# A5000_BasicBackplane.net
KiCad netlist of a schematic drawn in Altium Designer
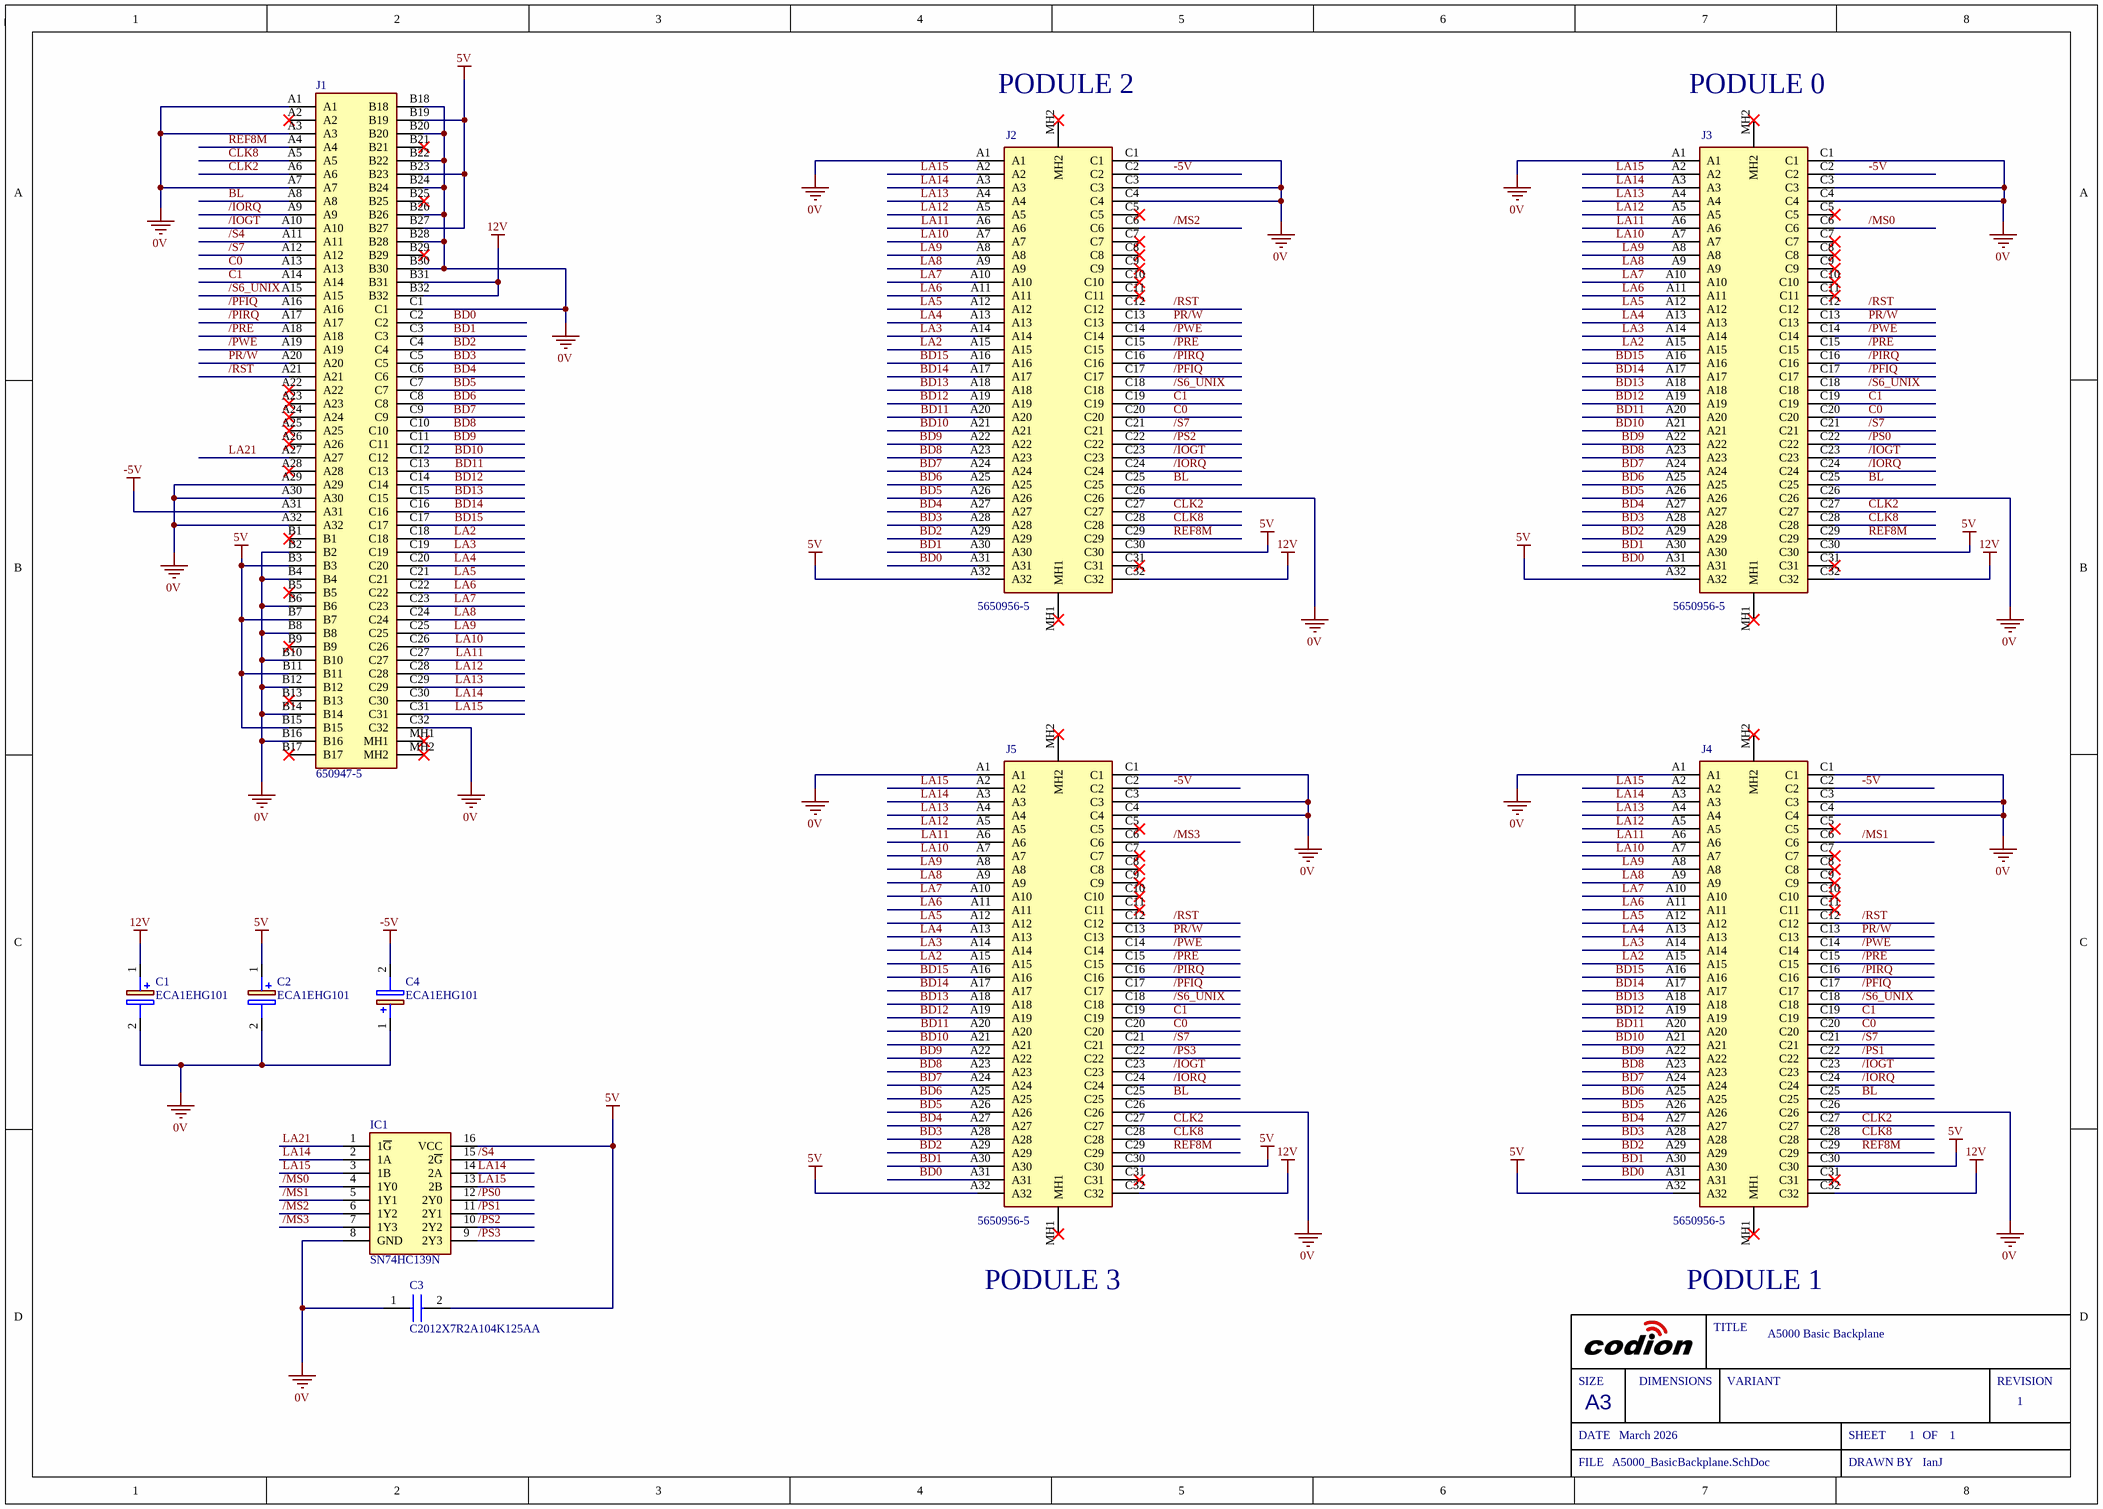
[diagram p0: A5000_BasicBackplane.SchDoc]

(export (version "E")
  (design (tool "Eeschema 10.0.6"))
  (components
    (comp (ref "C1")
      (value "ECA1EHG101")
      (footprint "SamacSys:CAPPRD250W55D630H1220")
      (description "Capacitor Polarised")
      (libsource (lib "*") (part "ECA1EHG101"))
    )
    (comp (ref "C2")
      (value "ECA1EHG101")
      (footprint "SamacSys:CAPPRD250W55D630H1220")
      (description "Capacitor Polarised")
      (libsource (lib "*") (part "ECA1EHG101"))
    )
    (comp (ref "C3")
      (value "C2012X7R2A104K125AA")
      (footprint "SamacSys:CAPC2012X145N")
      (description "Capacitor")
      (fields (field (name "MOUSER PART NUMBER") "810-C2012X7R2A104K"))
      (libsource (lib "*") (part "C2012X7R2A104K125AA"))
    )
    (comp (ref "C4")
      (value "ECA1EHG101")
      (footprint "SamacSys:CAPPRD250W55D630H1220")
      (description "Capacitor Polarised")
      (libsource (lib "") (part "ECA1EHG101_1"))
    )
    (comp (ref "IC1")
      (value "SN74HC139N")
      (footprint "SamacSys:DIP794W53P254L1930H508Q16N")
      (description "Integrated Circuit")
      (fields (field (name "MOUSER PART NUMBER") "595-SN74HC139N"))
      (libsource (lib "*") (part "SN74HC139N"))
    )
    (comp (ref "J1")
      (value "650947-5")
      (footprint "SamacSys:6509475")
      (description "Connector")
      (fields (field (name "MOUSER PART NUMBER") "571-6509475"))
      (libsource (lib "*") (part "650947-5"))
    )
    (comp (ref "J2")
      (value "5650956-5")
      (footprint "SamacSys:56509565")
      (description "Connector")
      (fields (field (name "MOUSER PART NUMBER") "571-5650956-5"))
      (libsource (lib "*") (part "5650956-5"))
    )
    (comp (ref "J3")
      (value "5650956-5")
      (footprint "SamacSys:56509565")
      (description "Connector")
      (fields (field (name "MOUSER PART NUMBER") "571-5650956-5"))
      (libsource (lib "*") (part "5650956-5"))
    )
    (comp (ref "J4")
      (value "5650956-5")
      (footprint "SamacSys:56509565")
      (description "Connector")
      (fields (field (name "MOUSER PART NUMBER") "571-5650956-5"))
      (libsource (lib "*") (part "5650956-5"))
    )
    (comp (ref "J5")
      (value "5650956-5")
      (footprint "SamacSys:56509565")
      (description "Connector")
      (fields (field (name "MOUSER PART NUMBER") "571-5650956-5"))
      (libsource (lib "*") (part "5650956-5"))
    )
  )
  (nets
    (net (code "1") (name "-5V") (class "Default")
      (node (ref "C4") (pin "2") (pinfunction "-_2") (pintype "passive"))
      (node (ref "J1") (pin "A31") (pinfunction "A31_A31") (pintype "passive"))
      (node (ref "J2") (pin "C2") (pinfunction "C2_C2") (pintype "passive"))
      (node (ref "J3") (pin "C2") (pinfunction "C2_C2") (pintype "passive"))
      (node (ref "J4") (pin "C2") (pinfunction "C2_C2") (pintype "passive"))
      (node (ref "J5") (pin "C2") (pinfunction "C2_C2") (pintype "passive"))
    )
    (net (code "2") (name "/BD0") (class "Default")
      (node (ref "J1") (pin "C2") (pinfunction "C2_C2") (pintype "passive"))
      (node (ref "J2") (pin "A31") (pinfunction "A31_A31") (pintype "passive"))
      (node (ref "J3") (pin "A31") (pinfunction "A31_A31") (pintype "passive"))
      (node (ref "J4") (pin "A31") (pinfunction "A31_A31") (pintype "passive"))
      (node (ref "J5") (pin "A31") (pinfunction "A31_A31") (pintype "passive"))
    )
    (net (code "3") (name "/BD1") (class "Default")
      (node (ref "J1") (pin "C3") (pinfunction "C3_C3") (pintype "passive"))
      (node (ref "J2") (pin "A30") (pinfunction "A30_A30") (pintype "passive"))
      (node (ref "J3") (pin "A30") (pinfunction "A30_A30") (pintype "passive"))
      (node (ref "J4") (pin "A30") (pinfunction "A30_A30") (pintype "passive"))
      (node (ref "J5") (pin "A30") (pinfunction "A30_A30") (pintype "passive"))
    )
    (net (code "4") (name "/BD2") (class "Default")
      (node (ref "J1") (pin "C4") (pinfunction "C4_C4") (pintype "passive"))
      (node (ref "J2") (pin "A29") (pinfunction "A29_A29") (pintype "passive"))
      (node (ref "J3") (pin "A29") (pinfunction "A29_A29") (pintype "passive"))
      (node (ref "J4") (pin "A29") (pinfunction "A29_A29") (pintype "passive"))
      (node (ref "J5") (pin "A29") (pinfunction "A29_A29") (pintype "passive"))
    )
    (net (code "5") (name "/BD3") (class "Default")
      (node (ref "J1") (pin "C5") (pinfunction "C5_C5") (pintype "passive"))
      (node (ref "J2") (pin "A28") (pinfunction "A28_A28") (pintype "passive"))
      (node (ref "J3") (pin "A28") (pinfunction "A28_A28") (pintype "passive"))
      (node (ref "J4") (pin "A28") (pinfunction "A28_A28") (pintype "passive"))
      (node (ref "J5") (pin "A28") (pinfunction "A28_A28") (pintype "passive"))
    )
    (net (code "6") (name "/BD4") (class "Default")
      (node (ref "J1") (pin "C6") (pinfunction "C6_C6") (pintype "passive"))
      (node (ref "J2") (pin "A27") (pinfunction "A27_A27") (pintype "passive"))
      (node (ref "J3") (pin "A27") (pinfunction "A27_A27") (pintype "passive"))
      (node (ref "J4") (pin "A27") (pinfunction "A27_A27") (pintype "passive"))
      (node (ref "J5") (pin "A27") (pinfunction "A27_A27") (pintype "passive"))
    )
    (net (code "7") (name "/BD5") (class "Default")
      (node (ref "J1") (pin "C7") (pinfunction "C7_C7") (pintype "passive"))
      (node (ref "J2") (pin "A26") (pinfunction "A26_A26") (pintype "passive"))
      (node (ref "J3") (pin "A26") (pinfunction "A26_A26") (pintype "passive"))
      (node (ref "J4") (pin "A26") (pinfunction "A26_A26") (pintype "passive"))
      (node (ref "J5") (pin "A26") (pinfunction "A26_A26") (pintype "passive"))
    )
    (net (code "8") (name "/BD6") (class "Default")
      (node (ref "J1") (pin "C8") (pinfunction "C8_C8") (pintype "passive"))
      (node (ref "J2") (pin "A25") (pinfunction "A25_A25") (pintype "passive"))
      (node (ref "J3") (pin "A25") (pinfunction "A25_A25") (pintype "passive"))
      (node (ref "J4") (pin "A25") (pinfunction "A25_A25") (pintype "passive"))
      (node (ref "J5") (pin "A25") (pinfunction "A25_A25") (pintype "passive"))
    )
    (net (code "9") (name "/BD7") (class "Default")
      (node (ref "J1") (pin "C9") (pinfunction "C9_C9") (pintype "passive"))
      (node (ref "J2") (pin "A24") (pinfunction "A24_A24") (pintype "passive"))
      (node (ref "J3") (pin "A24") (pinfunction "A24_A24") (pintype "passive"))
      (node (ref "J4") (pin "A24") (pinfunction "A24_A24") (pintype "passive"))
      (node (ref "J5") (pin "A24") (pinfunction "A24_A24") (pintype "passive"))
    )
    (net (code "10") (name "/BD8") (class "Default")
      (node (ref "J1") (pin "C10") (pinfunction "C10_C10") (pintype "passive"))
      (node (ref "J2") (pin "A23") (pinfunction "A23_A23") (pintype "passive"))
      (node (ref "J3") (pin "A23") (pinfunction "A23_A23") (pintype "passive"))
      (node (ref "J4") (pin "A23") (pinfunction "A23_A23") (pintype "passive"))
      (node (ref "J5") (pin "A23") (pinfunction "A23_A23") (pintype "passive"))
    )
    (net (code "11") (name "/BD9") (class "Default")
      (node (ref "J1") (pin "C11") (pinfunction "C11_C11") (pintype "passive"))
      (node (ref "J2") (pin "A22") (pinfunction "A22_A22") (pintype "passive"))
      (node (ref "J3") (pin "A22") (pinfunction "A22_A22") (pintype "passive"))
      (node (ref "J4") (pin "A22") (pinfunction "A22_A22") (pintype "passive"))
      (node (ref "J5") (pin "A22") (pinfunction "A22_A22") (pintype "passive"))
    )
    (net (code "12") (name "/BD10") (class "Default")
      (node (ref "J1") (pin "C12") (pinfunction "C12_C12") (pintype "passive"))
      (node (ref "J2") (pin "A21") (pinfunction "A21_A21") (pintype "passive"))
      (node (ref "J3") (pin "A21") (pinfunction "A21_A21") (pintype "passive"))
      (node (ref "J4") (pin "A21") (pinfunction "A21_A21") (pintype "passive"))
      (node (ref "J5") (pin "A21") (pinfunction "A21_A21") (pintype "passive"))
    )
    (net (code "13") (name "/BD11") (class "Default")
      (node (ref "J1") (pin "C13") (pinfunction "C13_C13") (pintype "passive"))
      (node (ref "J2") (pin "A20") (pinfunction "A20_A20") (pintype "passive"))
      (node (ref "J3") (pin "A20") (pinfunction "A20_A20") (pintype "passive"))
      (node (ref "J4") (pin "A20") (pinfunction "A20_A20") (pintype "passive"))
      (node (ref "J5") (pin "A20") (pinfunction "A20_A20") (pintype "passive"))
    )
    (net (code "14") (name "/BD12") (class "Default")
      (node (ref "J1") (pin "C14") (pinfunction "C14_C14") (pintype "passive"))
      (node (ref "J2") (pin "A19") (pinfunction "A19_A19") (pintype "passive"))
      (node (ref "J3") (pin "A19") (pinfunction "A19_A19") (pintype "passive"))
      (node (ref "J4") (pin "A19") (pinfunction "A19_A19") (pintype "passive"))
      (node (ref "J5") (pin "A19") (pinfunction "A19_A19") (pintype "passive"))
    )
    (net (code "15") (name "/BD13") (class "Default")
      (node (ref "J1") (pin "C15") (pinfunction "C15_C15") (pintype "passive"))
      (node (ref "J2") (pin "A18") (pinfunction "A18_A18") (pintype "passive"))
      (node (ref "J3") (pin "A18") (pinfunction "A18_A18") (pintype "passive"))
      (node (ref "J4") (pin "A18") (pinfunction "A18_A18") (pintype "passive"))
      (node (ref "J5") (pin "A18") (pinfunction "A18_A18") (pintype "passive"))
    )
    (net (code "16") (name "/BD14") (class "Default")
      (node (ref "J1") (pin "C16") (pinfunction "C16_C16") (pintype "passive"))
      (node (ref "J2") (pin "A17") (pinfunction "A17_A17") (pintype "passive"))
      (node (ref "J3") (pin "A17") (pinfunction "A17_A17") (pintype "passive"))
      (node (ref "J4") (pin "A17") (pinfunction "A17_A17") (pintype "passive"))
      (node (ref "J5") (pin "A17") (pinfunction "A17_A17") (pintype "passive"))
    )
    (net (code "17") (name "/BD15") (class "Default")
      (node (ref "J1") (pin "C17") (pinfunction "C17_C17") (pintype "passive"))
      (node (ref "J2") (pin "A16") (pinfunction "A16_A16") (pintype "passive"))
      (node (ref "J3") (pin "A16") (pinfunction "A16_A16") (pintype "passive"))
      (node (ref "J4") (pin "A16") (pinfunction "A16_A16") (pintype "passive"))
      (node (ref "J5") (pin "A16") (pinfunction "A16_A16") (pintype "passive"))
    )
    (net (code "18") (name "/BL") (class "Default")
      (node (ref "J1") (pin "A8") (pinfunction "A8_A8") (pintype "passive"))
      (node (ref "J2") (pin "C25") (pinfunction "C25_C25") (pintype "passive"))
      (node (ref "J3") (pin "C25") (pinfunction "C25_C25") (pintype "passive"))
      (node (ref "J4") (pin "C25") (pinfunction "C25_C25") (pintype "passive"))
      (node (ref "J5") (pin "C25") (pinfunction "C25_C25") (pintype "passive"))
    )
    (net (code "19") (name "/C0") (class "Default")
      (node (ref "J1") (pin "A13") (pinfunction "A13_A13") (pintype "passive"))
      (node (ref "J2") (pin "C20") (pinfunction "C20_C20") (pintype "passive"))
      (node (ref "J3") (pin "C20") (pinfunction "C20_C20") (pintype "passive"))
      (node (ref "J4") (pin "C20") (pinfunction "C20_C20") (pintype "passive"))
      (node (ref "J5") (pin "C20") (pinfunction "C20_C20") (pintype "passive"))
    )
    (net (code "20") (name "/C1") (class "Default")
      (node (ref "J1") (pin "A14") (pinfunction "A14_A14") (pintype "passive"))
      (node (ref "J2") (pin "C19") (pinfunction "C19_C19") (pintype "passive"))
      (node (ref "J3") (pin "C19") (pinfunction "C19_C19") (pintype "passive"))
      (node (ref "J4") (pin "C19") (pinfunction "C19_C19") (pintype "passive"))
      (node (ref "J5") (pin "C19") (pinfunction "C19_C19") (pintype "passive"))
    )
    (net (code "21") (name "/CLK2") (class "Default")
      (node (ref "J1") (pin "A6") (pinfunction "A6_A6") (pintype "passive"))
      (node (ref "J2") (pin "C27") (pinfunction "C27_C27") (pintype "passive"))
      (node (ref "J3") (pin "C27") (pinfunction "C27_C27") (pintype "passive"))
      (node (ref "J4") (pin "C27") (pinfunction "C27_C27") (pintype "passive"))
      (node (ref "J5") (pin "C27") (pinfunction "C27_C27") (pintype "passive"))
    )
    (net (code "22") (name "/CLK8") (class "Default")
      (node (ref "J1") (pin "A5") (pinfunction "A5_A5") (pintype "passive"))
      (node (ref "J2") (pin "C28") (pinfunction "C28_C28") (pintype "passive"))
      (node (ref "J3") (pin "C28") (pinfunction "C28_C28") (pintype "passive"))
      (node (ref "J4") (pin "C28") (pinfunction "C28_C28") (pintype "passive"))
      (node (ref "J5") (pin "C28") (pinfunction "C28_C28") (pintype "passive"))
    )
    (net (code "23") (name "/LA2") (class "Default")
      (node (ref "J1") (pin "C18") (pinfunction "C18_C18") (pintype "passive"))
      (node (ref "J2") (pin "A15") (pinfunction "A15_A15") (pintype "passive"))
      (node (ref "J3") (pin "A15") (pinfunction "A15_A15") (pintype "passive"))
      (node (ref "J4") (pin "A15") (pinfunction "A15_A15") (pintype "passive"))
      (node (ref "J5") (pin "A15") (pinfunction "A15_A15") (pintype "passive"))
    )
    (net (code "24") (name "/LA3") (class "Default")
      (node (ref "J1") (pin "C19") (pinfunction "C19_C19") (pintype "passive"))
      (node (ref "J2") (pin "A14") (pinfunction "A14_A14") (pintype "passive"))
      (node (ref "J3") (pin "A14") (pinfunction "A14_A14") (pintype "passive"))
      (node (ref "J4") (pin "A14") (pinfunction "A14_A14") (pintype "passive"))
      (node (ref "J5") (pin "A14") (pinfunction "A14_A14") (pintype "passive"))
    )
    (net (code "25") (name "/LA4") (class "Default")
      (node (ref "J1") (pin "C20") (pinfunction "C20_C20") (pintype "passive"))
      (node (ref "J2") (pin "A13") (pinfunction "A13_A13") (pintype "passive"))
      (node (ref "J3") (pin "A13") (pinfunction "A13_A13") (pintype "passive"))
      (node (ref "J4") (pin "A13") (pinfunction "A13_A13") (pintype "passive"))
      (node (ref "J5") (pin "A13") (pinfunction "A13_A13") (pintype "passive"))
    )
    (net (code "26") (name "/LA5") (class "Default")
      (node (ref "J1") (pin "C21") (pinfunction "C21_C21") (pintype "passive"))
      (node (ref "J2") (pin "A12") (pinfunction "A12_A12") (pintype "passive"))
      (node (ref "J3") (pin "A12") (pinfunction "A12_A12") (pintype "passive"))
      (node (ref "J4") (pin "A12") (pinfunction "A12_A12") (pintype "passive"))
      (node (ref "J5") (pin "A12") (pinfunction "A12_A12") (pintype "passive"))
    )
    (net (code "27") (name "/LA6") (class "Default")
      (node (ref "J1") (pin "C22") (pinfunction "C22_C22") (pintype "passive"))
      (node (ref "J2") (pin "A11") (pinfunction "A11_A11") (pintype "passive"))
      (node (ref "J3") (pin "A11") (pinfunction "A11_A11") (pintype "passive"))
      (node (ref "J4") (pin "A11") (pinfunction "A11_A11") (pintype "passive"))
      (node (ref "J5") (pin "A11") (pinfunction "A11_A11") (pintype "passive"))
    )
    (net (code "28") (name "/LA7") (class "Default")
      (node (ref "J1") (pin "C23") (pinfunction "C23_C23") (pintype "passive"))
      (node (ref "J2") (pin "A10") (pinfunction "A10_A10") (pintype "passive"))
      (node (ref "J3") (pin "A10") (pinfunction "A10_A10") (pintype "passive"))
      (node (ref "J4") (pin "A10") (pinfunction "A10_A10") (pintype "passive"))
      (node (ref "J5") (pin "A10") (pinfunction "A10_A10") (pintype "passive"))
    )
    (net (code "29") (name "/LA8") (class "Default")
      (node (ref "J1") (pin "C24") (pinfunction "C24_C24") (pintype "passive"))
      (node (ref "J2") (pin "A9") (pinfunction "A9_A9") (pintype "passive"))
      (node (ref "J3") (pin "A9") (pinfunction "A9_A9") (pintype "passive"))
      (node (ref "J4") (pin "A9") (pinfunction "A9_A9") (pintype "passive"))
      (node (ref "J5") (pin "A9") (pinfunction "A9_A9") (pintype "passive"))
    )
    (net (code "30") (name "/LA9") (class "Default")
      (node (ref "J1") (pin "C25") (pinfunction "C25_C25") (pintype "passive"))
      (node (ref "J2") (pin "A8") (pinfunction "A8_A8") (pintype "passive"))
      (node (ref "J3") (pin "A8") (pinfunction "A8_A8") (pintype "passive"))
      (node (ref "J4") (pin "A8") (pinfunction "A8_A8") (pintype "passive"))
      (node (ref "J5") (pin "A8") (pinfunction "A8_A8") (pintype "passive"))
    )
    (net (code "31") (name "/LA10") (class "Default")
      (node (ref "J1") (pin "C26") (pinfunction "C26_C26") (pintype "passive"))
      (node (ref "J2") (pin "A7") (pinfunction "A7_A7") (pintype "passive"))
      (node (ref "J3") (pin "A7") (pinfunction "A7_A7") (pintype "passive"))
      (node (ref "J4") (pin "A7") (pinfunction "A7_A7") (pintype "passive"))
      (node (ref "J5") (pin "A7") (pinfunction "A7_A7") (pintype "passive"))
    )
    (net (code "32") (name "/LA11") (class "Default")
      (node (ref "J1") (pin "C27") (pinfunction "C27_C27") (pintype "passive"))
      (node (ref "J2") (pin "A6") (pinfunction "A6_A6") (pintype "passive"))
      (node (ref "J3") (pin "A6") (pinfunction "A6_A6") (pintype "passive"))
      (node (ref "J4") (pin "A6") (pinfunction "A6_A6") (pintype "passive"))
      (node (ref "J5") (pin "A6") (pinfunction "A6_A6") (pintype "passive"))
    )
    (net (code "33") (name "/LA12") (class "Default")
      (node (ref "J1") (pin "C28") (pinfunction "C28_C28") (pintype "passive"))
      (node (ref "J2") (pin "A5") (pinfunction "A5_A5") (pintype "passive"))
      (node (ref "J3") (pin "A5") (pinfunction "A5_A5") (pintype "passive"))
      (node (ref "J4") (pin "A5") (pinfunction "A5_A5") (pintype "passive"))
      (node (ref "J5") (pin "A5") (pinfunction "A5_A5") (pintype "passive"))
    )
    (net (code "34") (name "/LA13") (class "Default")
      (node (ref "J1") (pin "C29") (pinfunction "C29_C29") (pintype "passive"))
      (node (ref "J2") (pin "A4") (pinfunction "A4_A4") (pintype "passive"))
      (node (ref "J3") (pin "A4") (pinfunction "A4_A4") (pintype "passive"))
      (node (ref "J4") (pin "A4") (pinfunction "A4_A4") (pintype "passive"))
      (node (ref "J5") (pin "A4") (pinfunction "A4_A4") (pintype "passive"))
    )
    (net (code "35") (name "/LA14") (class "Default")
      (node (ref "IC1") (pin "14") (pinfunction "2A_14") (pintype "passive"))
      (node (ref "IC1") (pin "2") (pinfunction "1A_2") (pintype "passive"))
      (node (ref "J1") (pin "C30") (pinfunction "C30_C30") (pintype "passive"))
      (node (ref "J2") (pin "A3") (pinfunction "A3_A3") (pintype "passive"))
      (node (ref "J3") (pin "A3") (pinfunction "A3_A3") (pintype "passive"))
      (node (ref "J4") (pin "A3") (pinfunction "A3_A3") (pintype "passive"))
      (node (ref "J5") (pin "A3") (pinfunction "A3_A3") (pintype "passive"))
    )
    (net (code "36") (name "/LA15") (class "Default")
      (node (ref "IC1") (pin "13") (pinfunction "2B_13") (pintype "passive"))
      (node (ref "IC1") (pin "3") (pinfunction "1B_3") (pintype "passive"))
      (node (ref "J1") (pin "C31") (pinfunction "C31_C31") (pintype "passive"))
      (node (ref "J2") (pin "A2") (pinfunction "A2_A2") (pintype "passive"))
      (node (ref "J3") (pin "A2") (pinfunction "A2_A2") (pintype "passive"))
      (node (ref "J4") (pin "A2") (pinfunction "A2_A2") (pintype "passive"))
      (node (ref "J5") (pin "A2") (pinfunction "A2_A2") (pintype "passive"))
    )
    (net (code "37") (name "/LA21") (class "Default")
      (node (ref "IC1") (pin "1") (pinfunction "1~{G}_1") (pintype "passive"))
      (node (ref "J1") (pin "A27") (pinfunction "A27_A27") (pintype "passive"))
    )
    (net (code "38") (name "/PR{slash}W") (class "Default")
      (node (ref "J1") (pin "A20") (pinfunction "A20_A20") (pintype "passive"))
      (node (ref "J2") (pin "C13") (pinfunction "C13_C13") (pintype "passive"))
      (node (ref "J3") (pin "C13") (pinfunction "C13_C13") (pintype "passive"))
      (node (ref "J4") (pin "C13") (pinfunction "C13_C13") (pintype "passive"))
      (node (ref "J5") (pin "C13") (pinfunction "C13_C13") (pintype "passive"))
    )
    (net (code "39") (name "/REF8M") (class "Default")
      (node (ref "J1") (pin "A4") (pinfunction "A4_A4") (pintype "passive"))
      (node (ref "J2") (pin "C29") (pinfunction "C29_C29") (pintype "passive"))
      (node (ref "J3") (pin "C29") (pinfunction "C29_C29") (pintype "passive"))
      (node (ref "J4") (pin "C29") (pinfunction "C29_C29") (pintype "passive"))
      (node (ref "J5") (pin "C29") (pinfunction "C29_C29") (pintype "passive"))
    )
    (net (code "40") (name "/{slash}IOGT") (class "Default")
      (node (ref "J1") (pin "A10") (pinfunction "A10_A10") (pintype "passive"))
      (node (ref "J2") (pin "C23") (pinfunction "C23_C23") (pintype "passive"))
      (node (ref "J3") (pin "C23") (pinfunction "C23_C23") (pintype "passive"))
      (node (ref "J4") (pin "C23") (pinfunction "C23_C23") (pintype "passive"))
      (node (ref "J5") (pin "C23") (pinfunction "C23_C23") (pintype "passive"))
    )
    (net (code "41") (name "/{slash}IORQ") (class "Default")
      (node (ref "J1") (pin "A9") (pinfunction "A9_A9") (pintype "passive"))
      (node (ref "J2") (pin "C24") (pinfunction "C24_C24") (pintype "passive"))
      (node (ref "J3") (pin "C24") (pinfunction "C24_C24") (pintype "passive"))
      (node (ref "J4") (pin "C24") (pinfunction "C24_C24") (pintype "passive"))
      (node (ref "J5") (pin "C24") (pinfunction "C24_C24") (pintype "passive"))
    )
    (net (code "42") (name "/{slash}MS0") (class "Default")
      (node (ref "IC1") (pin "4") (pinfunction "1Y0_4") (pintype "passive"))
      (node (ref "J3") (pin "C6") (pinfunction "C6_C6") (pintype "passive"))
    )
    (net (code "43") (name "/{slash}MS1") (class "Default")
      (node (ref "IC1") (pin "5") (pinfunction "1Y1_5") (pintype "passive"))
      (node (ref "J4") (pin "C6") (pinfunction "C6_C6") (pintype "passive"))
    )
    (net (code "44") (name "/{slash}MS2") (class "Default")
      (node (ref "IC1") (pin "6") (pinfunction "1Y2_6") (pintype "passive"))
      (node (ref "J2") (pin "C6") (pinfunction "C6_C6") (pintype "passive"))
    )
    (net (code "45") (name "/{slash}MS3") (class "Default")
      (node (ref "IC1") (pin "7") (pinfunction "1Y3_7") (pintype "passive"))
      (node (ref "J5") (pin "C6") (pinfunction "C6_C6") (pintype "passive"))
    )
    (net (code "46") (name "/{slash}PFIQ") (class "Default")
      (node (ref "J1") (pin "A16") (pinfunction "A16_A16") (pintype "passive"))
      (node (ref "J2") (pin "C17") (pinfunction "C17_C17") (pintype "passive"))
      (node (ref "J3") (pin "C17") (pinfunction "C17_C17") (pintype "passive"))
      (node (ref "J4") (pin "C17") (pinfunction "C17_C17") (pintype "passive"))
      (node (ref "J5") (pin "C17") (pinfunction "C17_C17") (pintype "passive"))
    )
    (net (code "47") (name "/{slash}PIRQ") (class "Default")
      (node (ref "J1") (pin "A17") (pinfunction "A17_A17") (pintype "passive"))
      (node (ref "J2") (pin "C16") (pinfunction "C16_C16") (pintype "passive"))
      (node (ref "J3") (pin "C16") (pinfunction "C16_C16") (pintype "passive"))
      (node (ref "J4") (pin "C16") (pinfunction "C16_C16") (pintype "passive"))
      (node (ref "J5") (pin "C16") (pinfunction "C16_C16") (pintype "passive"))
    )
    (net (code "48") (name "/{slash}PRE") (class "Default")
      (node (ref "J1") (pin "A18") (pinfunction "A18_A18") (pintype "passive"))
      (node (ref "J2") (pin "C15") (pinfunction "C15_C15") (pintype "passive"))
      (node (ref "J3") (pin "C15") (pinfunction "C15_C15") (pintype "passive"))
      (node (ref "J4") (pin "C15") (pinfunction "C15_C15") (pintype "passive"))
      (node (ref "J5") (pin "C15") (pinfunction "C15_C15") (pintype "passive"))
    )
    (net (code "49") (name "/{slash}PS0") (class "Default")
      (node (ref "IC1") (pin "12") (pinfunction "2Y0_12") (pintype "passive"))
      (node (ref "J3") (pin "C22") (pinfunction "C22_C22") (pintype "passive"))
    )
    (net (code "50") (name "/{slash}PS1") (class "Default")
      (node (ref "IC1") (pin "11") (pinfunction "2Y1_11") (pintype "passive"))
      (node (ref "J4") (pin "C22") (pinfunction "C22_C22") (pintype "passive"))
    )
    (net (code "51") (name "/{slash}PS2") (class "Default")
      (node (ref "IC1") (pin "10") (pinfunction "2Y2_10") (pintype "passive"))
      (node (ref "J2") (pin "C22") (pinfunction "C22_C22") (pintype "passive"))
    )
    (net (code "52") (name "/{slash}PS3") (class "Default")
      (node (ref "IC1") (pin "9") (pinfunction "2Y3_9") (pintype "passive"))
      (node (ref "J5") (pin "C22") (pinfunction "C22_C22") (pintype "passive"))
    )
    (net (code "53") (name "/{slash}PWE") (class "Default")
      (node (ref "J1") (pin "A19") (pinfunction "A19_A19") (pintype "passive"))
      (node (ref "J2") (pin "C14") (pinfunction "C14_C14") (pintype "passive"))
      (node (ref "J3") (pin "C14") (pinfunction "C14_C14") (pintype "passive"))
      (node (ref "J4") (pin "C14") (pinfunction "C14_C14") (pintype "passive"))
      (node (ref "J5") (pin "C14") (pinfunction "C14_C14") (pintype "passive"))
    )
    (net (code "54") (name "/{slash}RST") (class "Default")
      (node (ref "J1") (pin "A21") (pinfunction "A21_A21") (pintype "passive"))
      (node (ref "J2") (pin "C12") (pinfunction "C12_C12") (pintype "passive"))
      (node (ref "J3") (pin "C12") (pinfunction "C12_C12") (pintype "passive"))
      (node (ref "J4") (pin "C12") (pinfunction "C12_C12") (pintype "passive"))
      (node (ref "J5") (pin "C12") (pinfunction "C12_C12") (pintype "passive"))
    )
    (net (code "55") (name "/{slash}S4") (class "Default")
      (node (ref "IC1") (pin "15") (pinfunction "2~{G}_15") (pintype "passive"))
      (node (ref "J1") (pin "A11") (pinfunction "A11_A11") (pintype "passive"))
    )
    (net (code "56") (name "/{slash}S6_UNIX") (class "Default")
      (node (ref "J1") (pin "A15") (pinfunction "A15_A15") (pintype "passive"))
      (node (ref "J2") (pin "C18") (pinfunction "C18_C18") (pintype "passive"))
      (node (ref "J3") (pin "C18") (pinfunction "C18_C18") (pintype "passive"))
      (node (ref "J4") (pin "C18") (pinfunction "C18_C18") (pintype "passive"))
      (node (ref "J5") (pin "C18") (pinfunction "C18_C18") (pintype "passive"))
    )
    (net (code "57") (name "/{slash}S7") (class "Default")
      (node (ref "J1") (pin "A12") (pinfunction "A12_A12") (pintype "passive"))
      (node (ref "J2") (pin "C21") (pinfunction "C21_C21") (pintype "passive"))
      (node (ref "J3") (pin "C21") (pinfunction "C21_C21") (pintype "passive"))
      (node (ref "J4") (pin "C21") (pinfunction "C21_C21") (pintype "passive"))
      (node (ref "J5") (pin "C21") (pinfunction "C21_C21") (pintype "passive"))
    )
    (net (code "58") (name "0V") (class "Default")
      (node (ref "C1") (pin "2") (pinfunction "-_2") (pintype "passive"))
      (node (ref "C2") (pin "2") (pinfunction "-_2") (pintype "passive"))
      (node (ref "C3") (pin "1") (pinfunction "1_1") (pintype "passive"))
      (node (ref "C4") (pin "1") (pinfunction "+_1") (pintype "passive"))
      (node (ref "IC1") (pin "8") (pinfunction "GND_8") (pintype "passive"))
      (node (ref "J1") (pin "A1") (pinfunction "A1_A1") (pintype "passive"))
      (node (ref "J1") (pin "A29") (pinfunction "A29_A29") (pintype "passive"))
      (node (ref "J1") (pin "A3") (pinfunction "A3_A3") (pintype "passive"))
      (node (ref "J1") (pin "A30") (pinfunction "A30_A30") (pintype "passive"))
      (node (ref "J1") (pin "A32") (pinfunction "A32_A32") (pintype "passive"))
      (node (ref "J1") (pin "A7") (pinfunction "A7_A7") (pintype "passive"))
      (node (ref "J1") (pin "B10") (pinfunction "B10_B10") (pintype "passive"))
      (node (ref "J1") (pin "B12") (pinfunction "B12_B12") (pintype "passive"))
      (node (ref "J1") (pin "B14") (pinfunction "B14_B14") (pintype "passive"))
      (node (ref "J1") (pin "B16") (pinfunction "B16_B16") (pintype "passive"))
      (node (ref "J1") (pin "B18") (pinfunction "B18_B18") (pintype "passive"))
      (node (ref "J1") (pin "B2") (pinfunction "B2_B2") (pintype "passive"))
      (node (ref "J1") (pin "B20") (pinfunction "B20_B20") (pintype "passive"))
      (node (ref "J1") (pin "B22") (pinfunction "B22_B22") (pintype "passive"))
      (node (ref "J1") (pin "B24") (pinfunction "B24_B24") (pintype "passive"))
      (node (ref "J1") (pin "B26") (pinfunction "B26_B26") (pintype "passive"))
      (node (ref "J1") (pin "B28") (pinfunction "B28_B28") (pintype "passive"))
      (node (ref "J1") (pin "B30") (pinfunction "B30_B30") (pintype "passive"))
      (node (ref "J1") (pin "B4") (pinfunction "B4_B4") (pintype "passive"))
      (node (ref "J1") (pin "B6") (pinfunction "B6_B6") (pintype "passive"))
      (node (ref "J1") (pin "B8") (pinfunction "B8_B8") (pintype "passive"))
      (node (ref "J1") (pin "C1") (pinfunction "C1_C1") (pintype "passive"))
      (node (ref "J1") (pin "C32") (pinfunction "C32_C32") (pintype "passive"))
      (node (ref "J2") (pin "A1") (pinfunction "A1_A1") (pintype "passive"))
      (node (ref "J2") (pin "C1") (pinfunction "C1_C1") (pintype "passive"))
      (node (ref "J2") (pin "C26") (pinfunction "C26_C26") (pintype "passive"))
      (node (ref "J2") (pin "C3") (pinfunction "C3_C3") (pintype "passive"))
      (node (ref "J2") (pin "C4") (pinfunction "C4_C4") (pintype "passive"))
      (node (ref "J3") (pin "A1") (pinfunction "A1_A1") (pintype "passive"))
      (node (ref "J3") (pin "C1") (pinfunction "C1_C1") (pintype "passive"))
      (node (ref "J3") (pin "C26") (pinfunction "C26_C26") (pintype "passive"))
      (node (ref "J3") (pin "C3") (pinfunction "C3_C3") (pintype "passive"))
      (node (ref "J3") (pin "C4") (pinfunction "C4_C4") (pintype "passive"))
      (node (ref "J4") (pin "A1") (pinfunction "A1_A1") (pintype "passive"))
      (node (ref "J4") (pin "C1") (pinfunction "C1_C1") (pintype "passive"))
      (node (ref "J4") (pin "C26") (pinfunction "C26_C26") (pintype "passive"))
      (node (ref "J4") (pin "C3") (pinfunction "C3_C3") (pintype "passive"))
      (node (ref "J4") (pin "C4") (pinfunction "C4_C4") (pintype "passive"))
      (node (ref "J5") (pin "A1") (pinfunction "A1_A1") (pintype "passive"))
      (node (ref "J5") (pin "C1") (pinfunction "C1_C1") (pintype "passive"))
      (node (ref "J5") (pin "C26") (pinfunction "C26_C26") (pintype "passive"))
      (node (ref "J5") (pin "C3") (pinfunction "C3_C3") (pintype "passive"))
      (node (ref "J5") (pin "C4") (pinfunction "C4_C4") (pintype "passive"))
    )
    (net (code "59") (name "5V") (class "Default")
      (node (ref "C2") (pin "1") (pinfunction "+_1") (pintype "passive"))
      (node (ref "C3") (pin "2") (pinfunction "2_2") (pintype "passive"))
      (node (ref "IC1") (pin "16") (pinfunction "VCC_16") (pintype "passive"))
      (node (ref "J1") (pin "B11") (pinfunction "B11_B11") (pintype "passive"))
      (node (ref "J1") (pin "B15") (pinfunction "B15_B15") (pintype "passive"))
      (node (ref "J1") (pin "B19") (pinfunction "B19_B19") (pintype "passive"))
      (node (ref "J1") (pin "B23") (pinfunction "B23_B23") (pintype "passive"))
      (node (ref "J1") (pin "B27") (pinfunction "B27_B27") (pintype "passive"))
      (node (ref "J1") (pin "B3") (pinfunction "B3_B3") (pintype "passive"))
      (node (ref "J1") (pin "B7") (pinfunction "B7_B7") (pintype "passive"))
      (node (ref "J2") (pin "A32") (pinfunction "A32_A32") (pintype "passive"))
      (node (ref "J2") (pin "C30") (pinfunction "C30_C30") (pintype "passive"))
      (node (ref "J3") (pin "A32") (pinfunction "A32_A32") (pintype "passive"))
      (node (ref "J3") (pin "C30") (pinfunction "C30_C30") (pintype "passive"))
      (node (ref "J4") (pin "A32") (pinfunction "A32_A32") (pintype "passive"))
      (node (ref "J4") (pin "C30") (pinfunction "C30_C30") (pintype "passive"))
      (node (ref "J5") (pin "A32") (pinfunction "A32_A32") (pintype "passive"))
      (node (ref "J5") (pin "C30") (pinfunction "C30_C30") (pintype "passive"))
    )
    (net (code "60") (name "12V") (class "Default")
      (node (ref "C1") (pin "1") (pinfunction "+_1") (pintype "passive"))
      (node (ref "J1") (pin "B31") (pinfunction "B31_B31") (pintype "passive"))
      (node (ref "J1") (pin "B32") (pinfunction "B32_B32") (pintype "passive"))
      (node (ref "J2") (pin "C32") (pinfunction "C32_C32") (pintype "passive"))
      (node (ref "J3") (pin "C32") (pinfunction "C32_C32") (pintype "passive"))
      (node (ref "J4") (pin "C32") (pinfunction "C32_C32") (pintype "passive"))
      (node (ref "J5") (pin "C32") (pinfunction "C32_C32") (pintype "passive"))
    )
    (net (code "61") (name "unconnected-(J1-PadA2)") (class "Default")
      (node (ref "J1") (pin "A2") (pinfunction "A2_A2") (pintype "passive+no_connect"))
    )
    (net (code "62") (name "unconnected-(J1-PadA22)") (class "Default")
      (node (ref "J1") (pin "A22") (pinfunction "A22_A22") (pintype "passive+no_connect"))
    )
    (net (code "63") (name "unconnected-(J1-PadA23)") (class "Default")
      (node (ref "J1") (pin "A23") (pinfunction "A23_A23") (pintype "passive+no_connect"))
    )
    (net (code "64") (name "unconnected-(J1-PadA24)") (class "Default")
      (node (ref "J1") (pin "A24") (pinfunction "A24_A24") (pintype "passive+no_connect"))
    )
    (net (code "65") (name "unconnected-(J1-PadA25)") (class "Default")
      (node (ref "J1") (pin "A25") (pinfunction "A25_A25") (pintype "passive+no_connect"))
    )
    (net (code "66") (name "unconnected-(J1-PadA26)") (class "Default")
      (node (ref "J1") (pin "A26") (pinfunction "A26_A26") (pintype "passive+no_connect"))
    )
    (net (code "67") (name "unconnected-(J1-PadA28)") (class "Default")
      (node (ref "J1") (pin "A28") (pinfunction "A28_A28") (pintype "passive+no_connect"))
    )
    (net (code "68") (name "unconnected-(J1-PadB1)") (class "Default")
      (node (ref "J1") (pin "B1") (pinfunction "B1_B1") (pintype "passive+no_connect"))
    )
    (net (code "69") (name "unconnected-(J1-PadB5)") (class "Default")
      (node (ref "J1") (pin "B5") (pinfunction "B5_B5") (pintype "passive+no_connect"))
    )
    (net (code "70") (name "unconnected-(J1-PadB9)") (class "Default")
      (node (ref "J1") (pin "B9") (pinfunction "B9_B9") (pintype "passive+no_connect"))
    )
    (net (code "71") (name "unconnected-(J1-PadB13)") (class "Default")
      (node (ref "J1") (pin "B13") (pinfunction "B13_B13") (pintype "passive+no_connect"))
    )
    (net (code "72") (name "unconnected-(J1-PadB17)") (class "Default")
      (node (ref "J1") (pin "B17") (pinfunction "B17_B17") (pintype "passive+no_connect"))
    )
    (net (code "73") (name "unconnected-(J1-PadB21)") (class "Default")
      (node (ref "J1") (pin "B21") (pinfunction "B21_B21") (pintype "passive+no_connect"))
    )
    (net (code "74") (name "unconnected-(J1-PadB25)") (class "Default")
      (node (ref "J1") (pin "B25") (pinfunction "B25_B25") (pintype "passive+no_connect"))
    )
    (net (code "75") (name "unconnected-(J1-PadB29)") (class "Default")
      (node (ref "J1") (pin "B29") (pinfunction "B29_B29") (pintype "passive+no_connect"))
    )
    (net (code "76") (name "unconnected-(J1-PadMH1)") (class "Default")
      (node (ref "J1") (pin "MH1") (pinfunction "MH1_MH1") (pintype "passive+no_connect"))
    )
    (net (code "77") (name "unconnected-(J1-PadMH2)") (class "Default")
      (node (ref "J1") (pin "MH2") (pinfunction "MH2_MH2") (pintype "passive+no_connect"))
    )
    (net (code "78") (name "unconnected-(J2-PadC5)") (class "Default")
      (node (ref "J2") (pin "C5") (pinfunction "C5_C5") (pintype "passive+no_connect"))
    )
    (net (code "79") (name "unconnected-(J2-PadC7)") (class "Default")
      (node (ref "J2") (pin "C7") (pinfunction "C7_C7") (pintype "passive+no_connect"))
    )
    (net (code "80") (name "unconnected-(J2-PadC8)") (class "Default")
      (node (ref "J2") (pin "C8") (pinfunction "C8_C8") (pintype "passive+no_connect"))
    )
    (net (code "81") (name "unconnected-(J2-PadC9)") (class "Default")
      (node (ref "J2") (pin "C9") (pinfunction "C9_C9") (pintype "passive+no_connect"))
    )
    (net (code "82") (name "unconnected-(J2-PadC10)") (class "Default")
      (node (ref "J2") (pin "C10") (pinfunction "C10_C10") (pintype "passive+no_connect"))
    )
    (net (code "83") (name "unconnected-(J2-PadC11)") (class "Default")
      (node (ref "J2") (pin "C11") (pinfunction "C11_C11") (pintype "passive+no_connect"))
    )
    (net (code "84") (name "unconnected-(J2-PadC31)") (class "Default")
      (node (ref "J2") (pin "C31") (pinfunction "C31_C31") (pintype "passive+no_connect"))
    )
    (net (code "85") (name "unconnected-(J2-PadMH1)") (class "Default")
      (node (ref "J2") (pin "MH1") (pinfunction "MH1_MH1") (pintype "passive+no_connect"))
    )
    (net (code "86") (name "unconnected-(J2-PadMH2)") (class "Default")
      (node (ref "J2") (pin "MH2") (pinfunction "MH2_MH2") (pintype "passive+no_connect"))
    )
    (net (code "87") (name "unconnected-(J3-PadC5)") (class "Default")
      (node (ref "J3") (pin "C5") (pinfunction "C5_C5") (pintype "passive+no_connect"))
    )
    (net (code "88") (name "unconnected-(J3-PadC7)") (class "Default")
      (node (ref "J3") (pin "C7") (pinfunction "C7_C7") (pintype "passive+no_connect"))
    )
    (net (code "89") (name "unconnected-(J3-PadC8)") (class "Default")
      (node (ref "J3") (pin "C8") (pinfunction "C8_C8") (pintype "passive+no_connect"))
    )
    (net (code "90") (name "unconnected-(J3-PadC9)") (class "Default")
      (node (ref "J3") (pin "C9") (pinfunction "C9_C9") (pintype "passive+no_connect"))
    )
    (net (code "91") (name "unconnected-(J3-PadC10)") (class "Default")
      (node (ref "J3") (pin "C10") (pinfunction "C10_C10") (pintype "passive+no_connect"))
    )
    (net (code "92") (name "unconnected-(J3-PadC11)") (class "Default")
      (node (ref "J3") (pin "C11") (pinfunction "C11_C11") (pintype "passive+no_connect"))
    )
    (net (code "93") (name "unconnected-(J3-PadC31)") (class "Default")
      (node (ref "J3") (pin "C31") (pinfunction "C31_C31") (pintype "passive+no_connect"))
    )
    (net (code "94") (name "unconnected-(J3-PadMH1)") (class "Default")
      (node (ref "J3") (pin "MH1") (pinfunction "MH1_MH1") (pintype "passive+no_connect"))
    )
    (net (code "95") (name "unconnected-(J3-PadMH2)") (class "Default")
      (node (ref "J3") (pin "MH2") (pinfunction "MH2_MH2") (pintype "passive+no_connect"))
    )
    (net (code "96") (name "unconnected-(J4-PadC5)") (class "Default")
      (node (ref "J4") (pin "C5") (pinfunction "C5_C5") (pintype "passive+no_connect"))
    )
    (net (code "97") (name "unconnected-(J4-PadC7)") (class "Default")
      (node (ref "J4") (pin "C7") (pinfunction "C7_C7") (pintype "passive+no_connect"))
    )
    (net (code "98") (name "unconnected-(J4-PadC8)") (class "Default")
      (node (ref "J4") (pin "C8") (pinfunction "C8_C8") (pintype "passive+no_connect"))
    )
    (net (code "99") (name "unconnected-(J4-PadC9)") (class "Default")
      (node (ref "J4") (pin "C9") (pinfunction "C9_C9") (pintype "passive+no_connect"))
    )
    (net (code "100") (name "unconnected-(J4-PadC10)") (class "Default")
      (node (ref "J4") (pin "C10") (pinfunction "C10_C10") (pintype "passive+no_connect"))
    )
    (net (code "101") (name "unconnected-(J4-PadC11)") (class "Default")
      (node (ref "J4") (pin "C11") (pinfunction "C11_C11") (pintype "passive+no_connect"))
    )
    (net (code "102") (name "unconnected-(J4-PadC31)") (class "Default")
      (node (ref "J4") (pin "C31") (pinfunction "C31_C31") (pintype "passive+no_connect"))
    )
    (net (code "103") (name "unconnected-(J4-PadMH1)") (class "Default")
      (node (ref "J4") (pin "MH1") (pinfunction "MH1_MH1") (pintype "passive+no_connect"))
    )
    (net (code "104") (name "unconnected-(J4-PadMH2)") (class "Default")
      (node (ref "J4") (pin "MH2") (pinfunction "MH2_MH2") (pintype "passive+no_connect"))
    )
    (net (code "105") (name "unconnected-(J5-PadC5)") (class "Default")
      (node (ref "J5") (pin "C5") (pinfunction "C5_C5") (pintype "passive+no_connect"))
    )
    (net (code "106") (name "unconnected-(J5-PadC7)") (class "Default")
      (node (ref "J5") (pin "C7") (pinfunction "C7_C7") (pintype "passive+no_connect"))
    )
    (net (code "107") (name "unconnected-(J5-PadC8)") (class "Default")
      (node (ref "J5") (pin "C8") (pinfunction "C8_C8") (pintype "passive+no_connect"))
    )
    (net (code "108") (name "unconnected-(J5-PadC9)") (class "Default")
      (node (ref "J5") (pin "C9") (pinfunction "C9_C9") (pintype "passive+no_connect"))
    )
    (net (code "109") (name "unconnected-(J5-PadC10)") (class "Default")
      (node (ref "J5") (pin "C10") (pinfunction "C10_C10") (pintype "passive+no_connect"))
    )
    (net (code "110") (name "unconnected-(J5-PadC11)") (class "Default")
      (node (ref "J5") (pin "C11") (pinfunction "C11_C11") (pintype "passive+no_connect"))
    )
    (net (code "111") (name "unconnected-(J5-PadC31)") (class "Default")
      (node (ref "J5") (pin "C31") (pinfunction "C31_C31") (pintype "passive+no_connect"))
    )
    (net (code "112") (name "unconnected-(J5-PadMH1)") (class "Default")
      (node (ref "J5") (pin "MH1") (pinfunction "MH1_MH1") (pintype "passive+no_connect"))
    )
    (net (code "113") (name "unconnected-(J5-PadMH2)") (class "Default")
      (node (ref "J5") (pin "MH2") (pinfunction "MH2_MH2") (pintype "passive+no_connect"))
    )
  )
)
